# climbing_WS2812.net
KiCad netlist of a schematic drawn in EAGLE
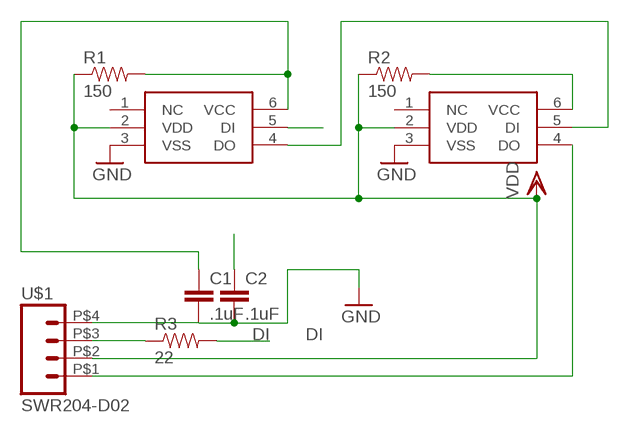
[diagram p0: schematic, sheet 1]

(export (version "E")
  (design (tool "Eeschema 10.0.6"))
  (components
    (comp (ref "C1")
      (value ".1uF")
      (footprint "eagle-import:0402-CAP")
      (libsource (lib "eagle-import") (part "CAP0402-CAP"))
    )
    (comp (ref "C2")
      (value ".1uF")
      (footprint "eagle-import:0402-CAP")
      (libsource (lib "eagle-import") (part "CAP0402-CAP"))
    )
    (comp (ref "R1")
      (value "150")
      (footprint "eagle-import:0402-RES")
      (libsource (lib "eagle-import") (part "RESISTOR0402-RES"))
    )
    (comp (ref "R2")
      (value "150")
      (footprint "eagle-import:0402-RES")
      (libsource (lib "eagle-import") (part "RESISTOR0402-RES"))
    )
    (comp (ref "R3")
      (value "22")
      (footprint "eagle-import:0402-RES")
      (libsource (lib "eagle-import") (part "RESISTOR0402-RES"))
    )
    (comp (ref "U$1")
      (value "SWR204-D02")
      (footprint "eagle-import:SWR204")
      (libsource (lib "eagle-import") (part "SWR204-D02"))
    )
    (comp (ref "U$2")
      (value "WS2812")
      (footprint "eagle-import:RGBLED5050")
      (libsource (lib "eagle-import") (part "WS2812"))
    )
    (comp (ref "U$3")
      (value "WS2812")
      (footprint "eagle-import:RGBLED5050")
      (libsource (lib "eagle-import") (part "WS2812"))
    )
  )
  (nets
    (net (code "1") (name "/DI") (class "Default")
      (node (ref "R3") (pin "2") (pinfunction "2_2") (pintype "passive"))
      (node (ref "U$2") (pin "5") (pinfunction "DI_5") (pintype "bidirectional"))
    )
    (net (code "2") (name "/VCC2") (class "Default")
      (node (ref "C2") (pin "1") (pinfunction "1_1") (pintype "passive"))
      (node (ref "R2") (pin "2") (pinfunction "2_2") (pintype "passive"))
      (node (ref "U$3") (pin "6") (pinfunction "VCC_6") (pintype "bidirectional"))
    )
    (net (code "3") (name "GND") (class "Default")
      (node (ref "C1") (pin "2") (pinfunction "2_2") (pintype "passive"))
      (node (ref "C2") (pin "2") (pinfunction "2_2") (pintype "passive"))
      (node (ref "U$1") (pin "P$4") (pinfunction "4_P$4") (pintype "passive"))
      (node (ref "U$2") (pin "3") (pinfunction "VSS_3") (pintype "bidirectional"))
      (node (ref "U$3") (pin "3") (pinfunction "VSS_3") (pintype "bidirectional"))
    )
    (net (code "4") (name "Net-(U$1-1)") (class "Default")
      (node (ref "U$1") (pin "P$1") (pinfunction "1_P$1") (pintype "passive"))
      (node (ref "U$3") (pin "4") (pinfunction "DO_4") (pintype "bidirectional"))
    )
    (net (code "5") (name "Net-(U$1-3)") (class "Default")
      (node (ref "R3") (pin "1") (pinfunction "1_1") (pintype "passive"))
      (node (ref "U$1") (pin "P$3") (pinfunction "3_P$3") (pintype "passive"))
    )
    (net (code "6") (name "Net-(U$2-DO)") (class "Default")
      (node (ref "U$2") (pin "4") (pinfunction "DO_4") (pintype "bidirectional"))
      (node (ref "U$3") (pin "5") (pinfunction "DI_5") (pintype "bidirectional"))
    )
    (net (code "7") (name "Net-(U$2-VCC)") (class "Default")
      (node (ref "C1") (pin "1") (pinfunction "1_1") (pintype "passive"))
      (node (ref "R1") (pin "2") (pinfunction "2_2") (pintype "passive"))
      (node (ref "U$2") (pin "6") (pinfunction "VCC_6") (pintype "bidirectional"))
    )
    (net (code "8") (name "VDD") (class "Default")
      (node (ref "R1") (pin "1") (pinfunction "1_1") (pintype "passive"))
      (node (ref "R2") (pin "1") (pinfunction "1_1") (pintype "passive"))
      (node (ref "U$1") (pin "P$2") (pinfunction "2_P$2") (pintype "passive"))
      (node (ref "U$2") (pin "2") (pinfunction "VDD_2") (pintype "bidirectional"))
      (node (ref "U$3") (pin "2") (pinfunction "VDD_2") (pintype "bidirectional"))
    )
    (net (code "9") (name "unconnected-(U$2-NC-Pad1)") (class "Default")
      (node (ref "U$2") (pin "1") (pinfunction "NC_1") (pintype "bidirectional"))
    )
    (net (code "10") (name "unconnected-(U$3-NC-Pad1)") (class "Default")
      (node (ref "U$3") (pin "1") (pinfunction "NC_1") (pintype "bidirectional"))
    )
  )
)
